# SparkFun_MP3_Breakout-VS1063.net
KiCad netlist of a schematic drawn in EAGLE
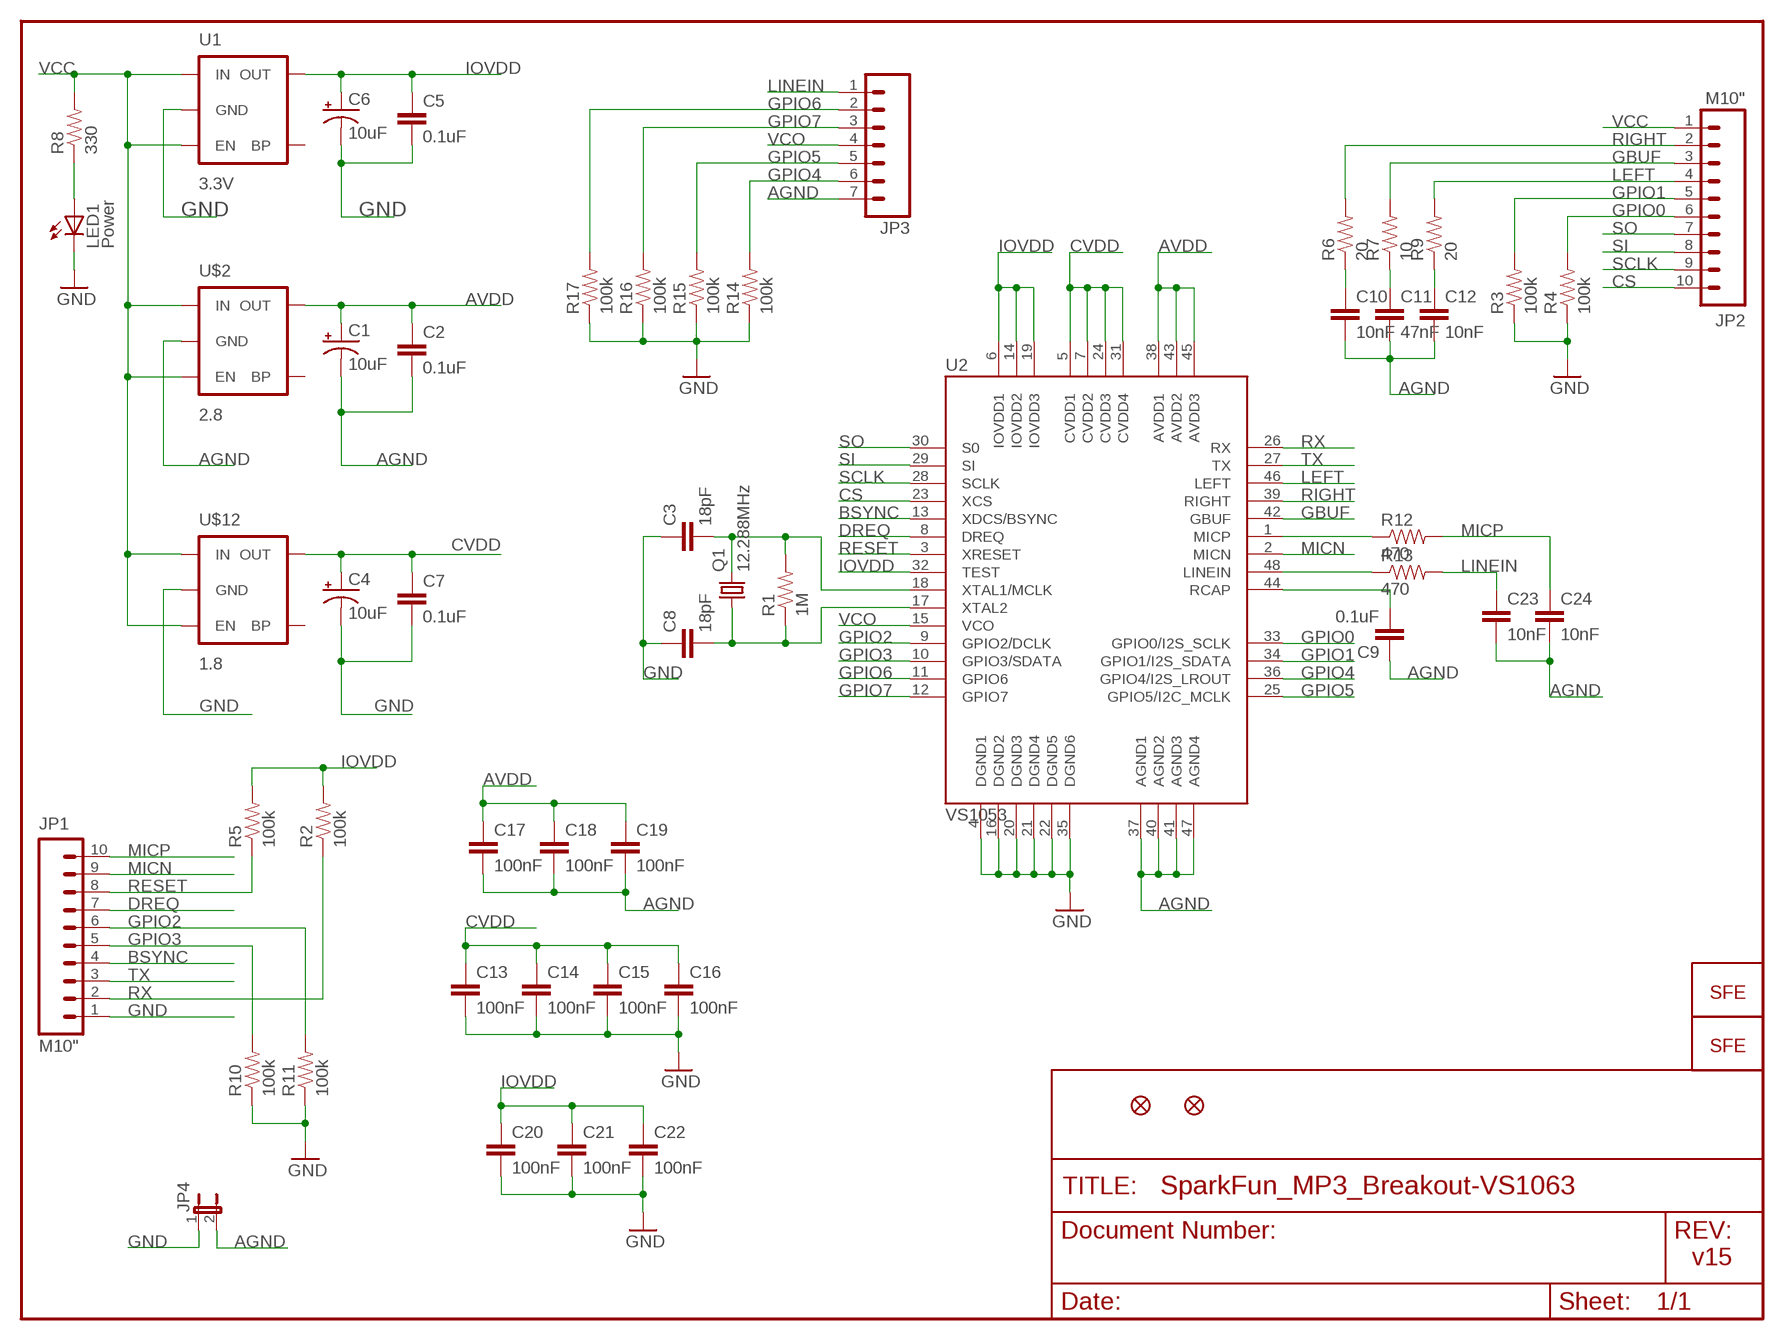
[diagram p0: schematic, sheet 1]

(export (version "E")
  (design (tool "Eeschema 10.0.6"))
  (components
    (comp (ref "C1")
      (value "10uF")
      (footprint "eagle-import:EIA3216")
      (libsource (lib "eagle-import") (part "CAP_POL1206"))
    )
    (comp (ref "C2")
      (value "0.1uF")
      (footprint "eagle-import:0402-CAP")
      (libsource (lib "eagle-import") (part "CAP0402-CAP"))
    )
    (comp (ref "C3")
      (value "18pF")
      (footprint "eagle-import:0402-CAP")
      (libsource (lib "eagle-import") (part "CAP0402-CAP"))
    )
    (comp (ref "C4")
      (value "10uF")
      (footprint "eagle-import:EIA3216")
      (libsource (lib "eagle-import") (part "CAP_POL1206"))
    )
    (comp (ref "C5")
      (value "0.1uF")
      (footprint "eagle-import:0402-CAP")
      (libsource (lib "eagle-import") (part "CAP0402-CAP"))
    )
    (comp (ref "C6")
      (value "10uF")
      (footprint "eagle-import:EIA3216")
      (libsource (lib "eagle-import") (part "CAP_POL1206"))
    )
    (comp (ref "C7")
      (value "0.1uF")
      (footprint "eagle-import:0402-CAP")
      (libsource (lib "eagle-import") (part "CAP0402-CAP"))
    )
    (comp (ref "C8")
      (value "18pF")
      (footprint "eagle-import:0402-CAP")
      (libsource (lib "eagle-import") (part "CAP0402-CAP"))
    )
    (comp (ref "C9")
      (value "0.1uF")
      (footprint "eagle-import:0402-CAP")
      (libsource (lib "eagle-import") (part "CAP0402-CAP"))
    )
    (comp (ref "C10")
      (value "10nF")
      (footprint "eagle-import:0402-CAP")
      (libsource (lib "eagle-import") (part "CAP0402-CAP"))
    )
    (comp (ref "C11")
      (value "47nF")
      (footprint "eagle-import:0402-CAP")
      (libsource (lib "eagle-import") (part "CAP0402-CAP"))
    )
    (comp (ref "C12")
      (value "10nF")
      (footprint "eagle-import:0402-CAP")
      (libsource (lib "eagle-import") (part "CAP0402-CAP"))
    )
    (comp (ref "C13")
      (value "100nF")
      (footprint "eagle-import:0402-CAP")
      (libsource (lib "eagle-import") (part "CAP0402-CAP"))
    )
    (comp (ref "C14")
      (value "100nF")
      (footprint "eagle-import:0402-CAP")
      (libsource (lib "eagle-import") (part "CAP0402-CAP"))
    )
    (comp (ref "C15")
      (value "100nF")
      (footprint "eagle-import:0402-CAP")
      (libsource (lib "eagle-import") (part "CAP0402-CAP"))
    )
    (comp (ref "C16")
      (value "100nF")
      (footprint "eagle-import:0402-CAP")
      (libsource (lib "eagle-import") (part "CAP0402-CAP"))
    )
    (comp (ref "C17")
      (value "100nF")
      (footprint "eagle-import:0402-CAP")
      (libsource (lib "eagle-import") (part "CAP0402-CAP"))
    )
    (comp (ref "C18")
      (value "100nF")
      (footprint "eagle-import:0402-CAP")
      (libsource (lib "eagle-import") (part "CAP0402-CAP"))
    )
    (comp (ref "C19")
      (value "100nF")
      (footprint "eagle-import:0402-CAP")
      (libsource (lib "eagle-import") (part "CAP0402-CAP"))
    )
    (comp (ref "C20")
      (value "100nF")
      (footprint "eagle-import:0402-CAP")
      (libsource (lib "eagle-import") (part "CAP0402-CAP"))
    )
    (comp (ref "C21")
      (value "100nF")
      (footprint "eagle-import:0402-CAP")
      (libsource (lib "eagle-import") (part "CAP0402-CAP"))
    )
    (comp (ref "C22")
      (value "100nF")
      (footprint "eagle-import:0402-CAP")
      (libsource (lib "eagle-import") (part "CAP0402-CAP"))
    )
    (comp (ref "C23")
      (value "10nF")
      (footprint "eagle-import:0402-CAP")
      (libsource (lib "eagle-import") (part "CAP0402-CAP"))
    )
    (comp (ref "C24")
      (value "10nF")
      (footprint "eagle-import:0402-CAP")
      (libsource (lib "eagle-import") (part "CAP0402-CAP"))
    )
    (comp (ref "JP1")
      (value "M10\"")
      (footprint "eagle-import:1X10")
      (libsource (lib "eagle-import") (part "M10{dblquote}"))
    )
    (comp (ref "JP2")
      (value "M10\"")
      (footprint "eagle-import:1X10")
      (libsource (lib "eagle-import") (part "M10{dblquote}"))
    )
    (comp (ref "JP3")
      (value "M07")
      (footprint "eagle-import:1X07")
      (libsource (lib "eagle-import") (part "M07"))
    )
    (comp (ref "JP4")
      (value "JUMPER-2SMD-NC")
      (footprint "eagle-import:SJ_2S")
      (libsource (lib "eagle-import") (part "JUMPER-2SMD-NC"))
    )
    (comp (ref "LED1")
      (value "Power")
      (footprint "eagle-import:LED-0603")
      (libsource (lib "eagle-import") (part "LED0603"))
    )
    (comp (ref "Q1")
      (value "12.288MHz")
      (footprint "eagle-import:CRYSTAL-SMD-5X3")
      (libsource (lib "eagle-import") (part "CRYSTAL5X3"))
    )
    (comp (ref "R1")
      (value "1M")
      (footprint "eagle-import:0402-RES")
      (libsource (lib "eagle-import") (part "RESISTOR0402-RES"))
    )
    (comp (ref "R2")
      (value "100k")
      (footprint "eagle-import:0402-RES")
      (libsource (lib "eagle-import") (part "RESISTOR0402-RES"))
    )
    (comp (ref "R3")
      (value "100k")
      (footprint "eagle-import:0402-RES")
      (libsource (lib "eagle-import") (part "RESISTOR0402-RES"))
    )
    (comp (ref "R4")
      (value "100k")
      (footprint "eagle-import:0402-RES")
      (libsource (lib "eagle-import") (part "RESISTOR0402-RES"))
    )
    (comp (ref "R5")
      (value "100k")
      (footprint "eagle-import:0402-RES")
      (libsource (lib "eagle-import") (part "RESISTOR0402-RES"))
    )
    (comp (ref "R6")
      (value "20")
      (footprint "eagle-import:0402-RES")
      (libsource (lib "eagle-import") (part "RESISTOR0402-RES"))
    )
    (comp (ref "R7")
      (value "10")
      (footprint "eagle-import:0402-RES")
      (libsource (lib "eagle-import") (part "RESISTOR0402-RES"))
    )
    (comp (ref "R8")
      (value "330")
      (footprint "eagle-import:0402-RES")
      (libsource (lib "eagle-import") (part "RESISTOR0402-RES"))
    )
    (comp (ref "R9")
      (value "20")
      (footprint "eagle-import:0402-RES")
      (libsource (lib "eagle-import") (part "RESISTOR0402-RES"))
    )
    (comp (ref "R10")
      (value "100k")
      (footprint "eagle-import:0402-RES")
      (libsource (lib "eagle-import") (part "RESISTOR0402-RES"))
    )
    (comp (ref "R11")
      (value "100k")
      (footprint "eagle-import:0402-RES")
      (libsource (lib "eagle-import") (part "RESISTOR0402-RES"))
    )
    (comp (ref "R12")
      (value "470")
      (footprint "eagle-import:0402-RES")
      (libsource (lib "eagle-import") (part "RESISTOR0402-RES"))
    )
    (comp (ref "R13")
      (value "470")
      (footprint "eagle-import:0402-RES")
      (libsource (lib "eagle-import") (part "RESISTOR0402-RES"))
    )
    (comp (ref "R14")
      (value "100k")
      (footprint "eagle-import:0402-RES")
      (libsource (lib "eagle-import") (part "RESISTOR0402-RES"))
    )
    (comp (ref "R15")
      (value "100k")
      (footprint "eagle-import:0402-RES")
      (libsource (lib "eagle-import") (part "RESISTOR0402-RES"))
    )
    (comp (ref "R16")
      (value "100k")
      (footprint "eagle-import:0402-RES")
      (libsource (lib "eagle-import") (part "RESISTOR0402-RES"))
    )
    (comp (ref "R17")
      (value "100k")
      (footprint "eagle-import:0402-RES")
      (libsource (lib "eagle-import") (part "RESISTOR0402-RES"))
    )
    (comp (ref "U$2")
      (value "2.8")
      (footprint "eagle-import:SC70")
      (libsource (lib "eagle-import") (part "V_REG_LDOSMD2"))
    )
    (comp (ref "U$4")
      (value "FIDUCIAL1X2")
      (footprint "eagle-import:FIDUCIAL-1X2")
      (libsource (lib "eagle-import") (part "FIDUCIAL1X2"))
    )
    (comp (ref "U$5")
      (value "FIDUCIAL1X2")
      (footprint "eagle-import:FIDUCIAL-1X2")
      (libsource (lib "eagle-import") (part "FIDUCIAL1X2"))
    )
    (comp (ref "U$6")
      (value "LOGO-SFESK")
      (footprint "eagle-import:SFE-LOGO-FLAME")
      (libsource (lib "eagle-import") (part "LOGO-SFESK"))
    )
    (comp (ref "U$7")
      (value "LOGO-SFENEW")
      (footprint "eagle-import:SFE-NEW-WEBLOGO")
      (libsource (lib "eagle-import") (part "LOGO-SFENEW"))
    )
    (comp (ref "U$12")
      (value "1.8")
      (footprint "eagle-import:SC70")
      (libsource (lib "eagle-import") (part "V_REG_LDOSMD2"))
    )
    (comp (ref "U1")
      (value "3.3V")
      (footprint "eagle-import:SOT23-5")
      (libsource (lib "eagle-import") (part "V_REG_LDOSMD"))
    )
    (comp (ref "U2")
      (value "VS1053")
      (footprint "eagle-import:LQFP-48")
      (libsource (lib "eagle-import") (part "VS1033"))
    )
  )
  (nets
    (net (code "1") (name "/AGND") (class "Default")
      (node (ref "C1") (pin "C") (pinfunction "-_C") (pintype "passive"))
      (node (ref "C10") (pin "2") (pinfunction "2_2") (pintype "passive"))
      (node (ref "C11") (pin "2") (pinfunction "2_2") (pintype "passive"))
      (node (ref "C12") (pin "2") (pinfunction "2_2") (pintype "passive"))
      (node (ref "C17") (pin "2") (pinfunction "2_2") (pintype "passive"))
      (node (ref "C18") (pin "2") (pinfunction "2_2") (pintype "passive"))
      (node (ref "C19") (pin "2") (pinfunction "2_2") (pintype "passive"))
      (node (ref "C2") (pin "2") (pinfunction "2_2") (pintype "passive"))
      (node (ref "C23") (pin "2") (pinfunction "2_2") (pintype "passive"))
      (node (ref "C24") (pin "2") (pinfunction "2_2") (pintype "passive"))
      (node (ref "C9") (pin "1") (pinfunction "1_1") (pintype "passive"))
      (node (ref "JP3") (pin "7") (pinfunction "7_7") (pintype "passive"))
      (node (ref "JP4") (pin "2") (pinfunction "2_2") (pintype "passive"))
      (node (ref "U$2") (pin "2") (pinfunction "GND_2") (pintype "input"))
      (node (ref "U2") (pin "37") (pinfunction "AGND1_37") (pintype "bidirectional"))
      (node (ref "U2") (pin "40") (pinfunction "AGND2_40") (pintype "bidirectional"))
      (node (ref "U2") (pin "41") (pinfunction "AGND3_41") (pintype "bidirectional"))
      (node (ref "U2") (pin "47") (pinfunction "AGND4_47") (pintype "bidirectional"))
    )
    (net (code "2") (name "/AVDD") (class "Default")
      (node (ref "C1") (pin "A") (pinfunction "+_A") (pintype "passive"))
      (node (ref "C17") (pin "1") (pinfunction "1_1") (pintype "passive"))
      (node (ref "C18") (pin "1") (pinfunction "1_1") (pintype "passive"))
      (node (ref "C19") (pin "1") (pinfunction "1_1") (pintype "passive"))
      (node (ref "C2") (pin "1") (pinfunction "1_1") (pintype "passive"))
      (node (ref "U$2") (pin "5") (pinfunction "OUT_5") (pintype "passive"))
      (node (ref "U2") (pin "38") (pinfunction "AVDD1_38") (pintype "bidirectional"))
      (node (ref "U2") (pin "43") (pinfunction "AVDD2_43") (pintype "bidirectional"))
      (node (ref "U2") (pin "45") (pinfunction "AVDD3_45") (pintype "bidirectional"))
    )
    (net (code "3") (name "/BSYNC") (class "Default")
      (node (ref "JP1") (pin "4") (pinfunction "4_4") (pintype "passive"))
      (node (ref "U2") (pin "13") (pinfunction "XDCS/BSYNC_13") (pintype "bidirectional"))
    )
    (net (code "4") (name "/CS") (class "Default")
      (node (ref "JP2") (pin "10") (pinfunction "10_10") (pintype "passive"))
      (node (ref "U2") (pin "23") (pinfunction "XCS_23") (pintype "bidirectional"))
    )
    (net (code "5") (name "/CVDD") (class "Default")
      (node (ref "C13") (pin "1") (pinfunction "1_1") (pintype "passive"))
      (node (ref "C14") (pin "1") (pinfunction "1_1") (pintype "passive"))
      (node (ref "C15") (pin "1") (pinfunction "1_1") (pintype "passive"))
      (node (ref "C16") (pin "1") (pinfunction "1_1") (pintype "passive"))
      (node (ref "C4") (pin "A") (pinfunction "+_A") (pintype "passive"))
      (node (ref "C7") (pin "1") (pinfunction "1_1") (pintype "passive"))
      (node (ref "U$12") (pin "5") (pinfunction "OUT_5") (pintype "passive"))
      (node (ref "U2") (pin "24") (pinfunction "CVDD3_24") (pintype "bidirectional"))
      (node (ref "U2") (pin "31") (pinfunction "CVDD4_31") (pintype "bidirectional"))
      (node (ref "U2") (pin "5") (pinfunction "CVDD1_5") (pintype "bidirectional"))
      (node (ref "U2") (pin "7") (pinfunction "CVDD2_7") (pintype "bidirectional"))
    )
    (net (code "6") (name "/DREQ") (class "Default")
      (node (ref "JP1") (pin "7") (pinfunction "7_7") (pintype "passive"))
      (node (ref "U2") (pin "8") (pinfunction "DREQ_8") (pintype "bidirectional"))
    )
    (net (code "7") (name "/GBUF") (class "Default")
      (node (ref "JP2") (pin "3") (pinfunction "3_3") (pintype "passive"))
      (node (ref "R7") (pin "2") (pinfunction "2_2") (pintype "passive"))
      (node (ref "U2") (pin "42") (pinfunction "GBUF_42") (pintype "bidirectional"))
    )
    (net (code "8") (name "/GPIO0") (class "Default")
      (node (ref "JP2") (pin "6") (pinfunction "6_6") (pintype "passive"))
      (node (ref "R4") (pin "2") (pinfunction "2_2") (pintype "passive"))
      (node (ref "U2") (pin "33") (pinfunction "GPIO0/I2S_SCLK_33") (pintype "bidirectional"))
    )
    (net (code "9") (name "/GPIO1") (class "Default")
      (node (ref "JP2") (pin "5") (pinfunction "5_5") (pintype "passive"))
      (node (ref "R3") (pin "2") (pinfunction "2_2") (pintype "passive"))
      (node (ref "U2") (pin "34") (pinfunction "GPIO1/I2S_SDATA_34") (pintype "bidirectional"))
    )
    (net (code "10") (name "/GPIO2") (class "Default")
      (node (ref "JP1") (pin "6") (pinfunction "6_6") (pintype "passive"))
      (node (ref "R11") (pin "2") (pinfunction "2_2") (pintype "passive"))
      (node (ref "U2") (pin "9") (pinfunction "GPIO2/DCLK_9") (pintype "bidirectional"))
    )
    (net (code "11") (name "/GPIO3") (class "Default")
      (node (ref "JP1") (pin "5") (pinfunction "5_5") (pintype "passive"))
      (node (ref "R10") (pin "2") (pinfunction "2_2") (pintype "passive"))
      (node (ref "U2") (pin "10") (pinfunction "GPIO3/SDATA_10") (pintype "bidirectional"))
    )
    (net (code "12") (name "/GPIO4") (class "Default")
      (node (ref "JP3") (pin "6") (pinfunction "6_6") (pintype "passive"))
      (node (ref "R14") (pin "2") (pinfunction "2_2") (pintype "passive"))
      (node (ref "U2") (pin "36") (pinfunction "GPIO4/I2S_LROUT_36") (pintype "bidirectional"))
    )
    (net (code "13") (name "/GPIO5") (class "Default")
      (node (ref "JP3") (pin "5") (pinfunction "5_5") (pintype "passive"))
      (node (ref "R15") (pin "2") (pinfunction "2_2") (pintype "passive"))
      (node (ref "U2") (pin "25") (pinfunction "GPIO5/I2C_MCLK_25") (pintype "bidirectional"))
    )
    (net (code "14") (name "/GPIO6") (class "Default")
      (node (ref "JP3") (pin "2") (pinfunction "2_2") (pintype "passive"))
      (node (ref "R17") (pin "2") (pinfunction "2_2") (pintype "passive"))
      (node (ref "U2") (pin "11") (pinfunction "GPIO6_11") (pintype "bidirectional"))
    )
    (net (code "15") (name "/GPIO7") (class "Default")
      (node (ref "JP3") (pin "3") (pinfunction "3_3") (pintype "passive"))
      (node (ref "R16") (pin "2") (pinfunction "2_2") (pintype "passive"))
      (node (ref "U2") (pin "12") (pinfunction "GPIO7_12") (pintype "bidirectional"))
    )
    (net (code "16") (name "/IOVDD") (class "Default")
      (node (ref "C20") (pin "1") (pinfunction "1_1") (pintype "passive"))
      (node (ref "C21") (pin "1") (pinfunction "1_1") (pintype "passive"))
      (node (ref "C22") (pin "1") (pinfunction "1_1") (pintype "passive"))
      (node (ref "C5") (pin "1") (pinfunction "1_1") (pintype "passive"))
      (node (ref "C6") (pin "A") (pinfunction "+_A") (pintype "passive"))
      (node (ref "R2") (pin "2") (pinfunction "2_2") (pintype "passive"))
      (node (ref "R5") (pin "2") (pinfunction "2_2") (pintype "passive"))
      (node (ref "U1") (pin "5") (pinfunction "OUT_5") (pintype "passive"))
      (node (ref "U2") (pin "14") (pinfunction "IOVDD2_14") (pintype "bidirectional"))
      (node (ref "U2") (pin "19") (pinfunction "IOVDD3_19") (pintype "bidirectional"))
      (node (ref "U2") (pin "32") (pinfunction "TEST_32") (pintype "bidirectional"))
      (node (ref "U2") (pin "6") (pinfunction "IOVDD1_6") (pintype "bidirectional"))
    )
    (net (code "17") (name "/LEFT") (class "Default")
      (node (ref "JP2") (pin "4") (pinfunction "4_4") (pintype "passive"))
      (node (ref "R9") (pin "2") (pinfunction "2_2") (pintype "passive"))
      (node (ref "U2") (pin "46") (pinfunction "LEFT_46") (pintype "bidirectional"))
    )
    (net (code "18") (name "/LINEIN") (class "Default")
      (node (ref "C23") (pin "1") (pinfunction "1_1") (pintype "passive"))
      (node (ref "JP3") (pin "1") (pinfunction "1_1") (pintype "passive"))
      (node (ref "R13") (pin "2") (pinfunction "2_2") (pintype "passive"))
    )
    (net (code "19") (name "/MICN") (class "Default")
      (node (ref "JP1") (pin "9") (pinfunction "9_9") (pintype "passive"))
      (node (ref "U2") (pin "2") (pinfunction "MICN_2") (pintype "bidirectional"))
    )
    (net (code "20") (name "/MICP") (class "Default")
      (node (ref "C24") (pin "1") (pinfunction "1_1") (pintype "passive"))
      (node (ref "JP1") (pin "10") (pinfunction "10_10") (pintype "passive"))
      (node (ref "R12") (pin "2") (pinfunction "2_2") (pintype "passive"))
    )
    (net (code "21") (name "/RESET") (class "Default")
      (node (ref "JP1") (pin "8") (pinfunction "8_8") (pintype "passive"))
      (node (ref "R5") (pin "1") (pinfunction "1_1") (pintype "passive"))
      (node (ref "U2") (pin "3") (pinfunction "XRESET_3") (pintype "bidirectional"))
    )
    (net (code "22") (name "/RIGHT") (class "Default")
      (node (ref "JP2") (pin "2") (pinfunction "2_2") (pintype "passive"))
      (node (ref "R6") (pin "2") (pinfunction "2_2") (pintype "passive"))
      (node (ref "U2") (pin "39") (pinfunction "RIGHT_39") (pintype "bidirectional"))
    )
    (net (code "23") (name "/RX") (class "Default")
      (node (ref "JP1") (pin "2") (pinfunction "2_2") (pintype "passive"))
      (node (ref "R2") (pin "1") (pinfunction "1_1") (pintype "passive"))
      (node (ref "U2") (pin "26") (pinfunction "RX_26") (pintype "bidirectional"))
    )
    (net (code "24") (name "/SCLK") (class "Default")
      (node (ref "JP2") (pin "9") (pinfunction "9_9") (pintype "passive"))
      (node (ref "U2") (pin "28") (pinfunction "SCLK_28") (pintype "bidirectional"))
    )
    (net (code "25") (name "/SI") (class "Default")
      (node (ref "JP2") (pin "8") (pinfunction "8_8") (pintype "passive"))
      (node (ref "U2") (pin "29") (pinfunction "SI_29") (pintype "bidirectional"))
    )
    (net (code "26") (name "/SO") (class "Default")
      (node (ref "JP2") (pin "7") (pinfunction "7_7") (pintype "passive"))
      (node (ref "U2") (pin "30") (pinfunction "S0_30") (pintype "bidirectional"))
    )
    (net (code "27") (name "/TX") (class "Default")
      (node (ref "JP1") (pin "3") (pinfunction "3_3") (pintype "passive"))
      (node (ref "U2") (pin "27") (pinfunction "TX_27") (pintype "bidirectional"))
    )
    (net (code "28") (name "/VCC") (class "Default")
      (node (ref "JP2") (pin "1") (pinfunction "1_1") (pintype "passive"))
      (node (ref "R8") (pin "2") (pinfunction "2_2") (pintype "passive"))
      (node (ref "U$12") (pin "1") (pinfunction "IN_1") (pintype "input"))
      (node (ref "U$12") (pin "3") (pinfunction "EN_3") (pintype "input"))
      (node (ref "U$2") (pin "1") (pinfunction "IN_1") (pintype "input"))
      (node (ref "U$2") (pin "3") (pinfunction "EN_3") (pintype "input"))
      (node (ref "U1") (pin "1") (pinfunction "IN_1") (pintype "input"))
      (node (ref "U1") (pin "3") (pinfunction "EN_3") (pintype "input"))
    )
    (net (code "29") (name "/VCO") (class "Default")
      (node (ref "JP3") (pin "4") (pinfunction "4_4") (pintype "passive"))
      (node (ref "U2") (pin "15") (pinfunction "VCO_15") (pintype "bidirectional"))
    )
    (net (code "30") (name "GND") (class "Default")
      (node (ref "C13") (pin "2") (pinfunction "2_2") (pintype "passive"))
      (node (ref "C14") (pin "2") (pinfunction "2_2") (pintype "passive"))
      (node (ref "C15") (pin "2") (pinfunction "2_2") (pintype "passive"))
      (node (ref "C16") (pin "2") (pinfunction "2_2") (pintype "passive"))
      (node (ref "C20") (pin "2") (pinfunction "2_2") (pintype "passive"))
      (node (ref "C21") (pin "2") (pinfunction "2_2") (pintype "passive"))
      (node (ref "C22") (pin "2") (pinfunction "2_2") (pintype "passive"))
      (node (ref "C3") (pin "1") (pinfunction "1_1") (pintype "passive"))
      (node (ref "C4") (pin "C") (pinfunction "-_C") (pintype "passive"))
      (node (ref "C5") (pin "2") (pinfunction "2_2") (pintype "passive"))
      (node (ref "C6") (pin "C") (pinfunction "-_C") (pintype "passive"))
      (node (ref "C7") (pin "2") (pinfunction "2_2") (pintype "passive"))
      (node (ref "C8") (pin "1") (pinfunction "1_1") (pintype "passive"))
      (node (ref "JP1") (pin "1") (pinfunction "1_1") (pintype "passive"))
      (node (ref "JP4") (pin "1") (pinfunction "1_1") (pintype "passive"))
      (node (ref "LED1") (pin "C") (pinfunction "C_C") (pintype "passive"))
      (node (ref "R10") (pin "1") (pinfunction "1_1") (pintype "passive"))
      (node (ref "R11") (pin "1") (pinfunction "1_1") (pintype "passive"))
      (node (ref "R14") (pin "1") (pinfunction "1_1") (pintype "passive"))
      (node (ref "R15") (pin "1") (pinfunction "1_1") (pintype "passive"))
      (node (ref "R16") (pin "1") (pinfunction "1_1") (pintype "passive"))
      (node (ref "R17") (pin "1") (pinfunction "1_1") (pintype "passive"))
      (node (ref "R3") (pin "1") (pinfunction "1_1") (pintype "passive"))
      (node (ref "R4") (pin "1") (pinfunction "1_1") (pintype "passive"))
      (node (ref "U$12") (pin "2") (pinfunction "GND_2") (pintype "input"))
      (node (ref "U1") (pin "2") (pinfunction "GND_2") (pintype "input"))
      (node (ref "U2") (pin "16") (pinfunction "DGND2_16") (pintype "bidirectional"))
      (node (ref "U2") (pin "20") (pinfunction "DGND3_20") (pintype "bidirectional"))
      (node (ref "U2") (pin "21") (pinfunction "DGND4_21") (pintype "bidirectional"))
      (node (ref "U2") (pin "22") (pinfunction "DGND5_22") (pintype "bidirectional"))
      (node (ref "U2") (pin "35") (pinfunction "DGND6_35") (pintype "bidirectional"))
      (node (ref "U2") (pin "4") (pinfunction "DGND1_4") (pintype "bidirectional"))
    )
    (net (code "31") (name "Net-(C10-Pad1)") (class "Default")
      (node (ref "C10") (pin "1") (pinfunction "1_1") (pintype "passive"))
      (node (ref "R6") (pin "1") (pinfunction "1_1") (pintype "passive"))
    )
    (net (code "32") (name "Net-(C11-Pad1)") (class "Default")
      (node (ref "C11") (pin "1") (pinfunction "1_1") (pintype "passive"))
      (node (ref "R7") (pin "1") (pinfunction "1_1") (pintype "passive"))
    )
    (net (code "33") (name "Net-(C12-Pad1)") (class "Default")
      (node (ref "C12") (pin "1") (pinfunction "1_1") (pintype "passive"))
      (node (ref "R9") (pin "1") (pinfunction "1_1") (pintype "passive"))
    )
    (net (code "34") (name "Net-(LED1-PadA)") (class "Default")
      (node (ref "LED1") (pin "A") (pinfunction "A_A") (pintype "passive"))
      (node (ref "R8") (pin "1") (pinfunction "1_1") (pintype "passive"))
    )
    (net (code "35") (name "Net-(Q1-2)") (class "Default")
      (node (ref "C3") (pin "2") (pinfunction "2_2") (pintype "passive"))
      (node (ref "Q1") (pin "3") (pinfunction "2_3") (pintype "passive"))
      (node (ref "R1") (pin "2") (pinfunction "2_2") (pintype "passive"))
      (node (ref "U2") (pin "18") (pinfunction "XTAL1/MCLK_18") (pintype "bidirectional"))
    )
    (net (code "36") (name "Net-(U2-LINEIN)") (class "Default")
      (node (ref "R13") (pin "1") (pinfunction "1_1") (pintype "passive"))
      (node (ref "U2") (pin "48") (pinfunction "LINEIN_48") (pintype "bidirectional"))
    )
    (net (code "37") (name "Net-(U2-MICP)") (class "Default")
      (node (ref "R12") (pin "1") (pinfunction "1_1") (pintype "passive"))
      (node (ref "U2") (pin "1") (pinfunction "MICP_1") (pintype "bidirectional"))
    )
    (net (code "38") (name "Net-(U2-RCAP)") (class "Default")
      (node (ref "C9") (pin "2") (pinfunction "2_2") (pintype "passive"))
      (node (ref "U2") (pin "44") (pinfunction "RCAP_44") (pintype "bidirectional"))
    )
    (net (code "39") (name "Net-(U2-XTAL2)") (class "Default")
      (node (ref "C8") (pin "2") (pinfunction "2_2") (pintype "passive"))
      (node (ref "Q1") (pin "1") (pinfunction "1_1") (pintype "passive"))
      (node (ref "R1") (pin "1") (pinfunction "1_1") (pintype "passive"))
      (node (ref "U2") (pin "17") (pinfunction "XTAL2_17") (pintype "bidirectional"))
    )
    (net (code "40") (name "unconnected-(U$2-BP-Pad4)") (class "Default")
      (node (ref "U$2") (pin "4") (pinfunction "BP_4") (pintype "input"))
    )
    (net (code "41") (name "unconnected-(U$12-BP-Pad4)") (class "Default")
      (node (ref "U$12") (pin "4") (pinfunction "BP_4") (pintype "input"))
    )
    (net (code "42") (name "unconnected-(U1-BP-Pad4)") (class "Default")
      (node (ref "U1") (pin "4") (pinfunction "BP_4") (pintype "input"))
    )
  )
)
